# QCopterFC_LED_Sch.net
KiCad netlist of a schematic drawn in Altium Designer
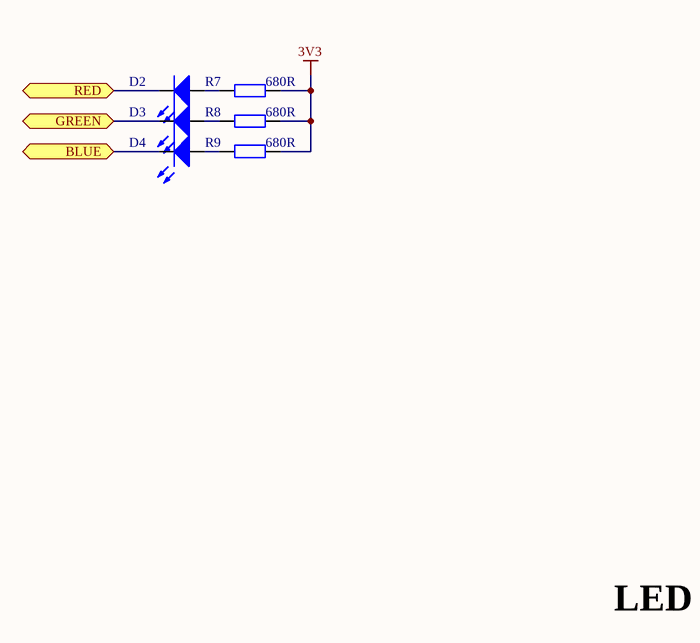
[diagram p0: QCopterFC_LED_Sch.SchDoc]

(export (version "E")
  (design (tool "Eeschema 10.0.6"))
  (components
    (comp (ref "D2")
      (value "LED_0603_RED")
      (footprint "PCB_Active:LED_0603_RED")
      (description "LED")
      (libsource (lib "SCH_Active") (part "LED_0603_RED"))
    )
    (comp (ref "D3")
      (value "LED_0603_GREEN")
      (footprint "PCB_Active:LED_0603_GREEN")
      (description "LED")
      (libsource (lib "SCH_Active") (part "LED_0603_GREEN"))
    )
    (comp (ref "D4")
      (value "LED_0603_BLUE")
      (footprint "PCB_Active:LED_0603_BLUE")
      (description "LED")
      (libsource (lib "SCH_Active") (part "LED_0603_BLUE"))
    )
    (comp (ref "R7")
      (value "680R")
      (footprint "PCB_Passive:RES_0603")
      (description "Resistor")
      (fields (field (name "Comment") "Res_0603"))
      (libsource (lib "SCH_Passive") (part "Res_0603"))
    )
    (comp (ref "R8")
      (value "680R")
      (footprint "PCB_Passive:RES_0603")
      (description "Resistor")
      (fields (field (name "Comment") "Res_0603"))
      (libsource (lib "SCH_Passive") (part "Res_0603"))
    )
    (comp (ref "R9")
      (value "680R")
      (footprint "PCB_Passive:RES_0603")
      (description "Resistor")
      (fields (field (name "Comment") "Res_0603"))
      (libsource (lib "SCH_Passive") (part "Res_0603"))
    )
  )
  (nets
    (net (code "1") (name "/BLUE") (class "Default")
      (node (ref "D4") (pin "2") (pinfunction "K_2") (pintype "passive"))
    )
    (net (code "2") (name "/GREEN") (class "Default")
      (node (ref "D3") (pin "2") (pinfunction "K_2") (pintype "passive"))
    )
    (net (code "3") (name "/RED") (class "Default")
      (node (ref "D2") (pin "2") (pinfunction "K_2") (pintype "passive"))
    )
    (net (code "4") (name "3V3") (class "Default")
      (node (ref "R7") (pin "2") (pinfunction "2_2") (pintype "passive"))
      (node (ref "R8") (pin "2") (pinfunction "2_2") (pintype "passive"))
      (node (ref "R9") (pin "2") (pinfunction "2_2") (pintype "passive"))
    )
    (net (code "5") (name "Net-(D2-A)") (class "Default")
      (node (ref "D2") (pin "1") (pinfunction "A_1") (pintype "passive"))
      (node (ref "R7") (pin "1") (pinfunction "1_1") (pintype "passive"))
    )
    (net (code "6") (name "Net-(D3-A)") (class "Default")
      (node (ref "D3") (pin "1") (pinfunction "A_1") (pintype "passive"))
      (node (ref "R8") (pin "1") (pinfunction "1_1") (pintype "passive"))
    )
    (net (code "7") (name "Net-(D4-A)") (class "Default")
      (node (ref "D4") (pin "1") (pinfunction "A_1") (pintype "passive"))
      (node (ref "R9") (pin "1") (pinfunction "1_1") (pintype "passive"))
    )
  )
)
